# 2020-10-27_AD590_HIH-4031.net
KiCad netlist of a schematic drawn in EAGLE
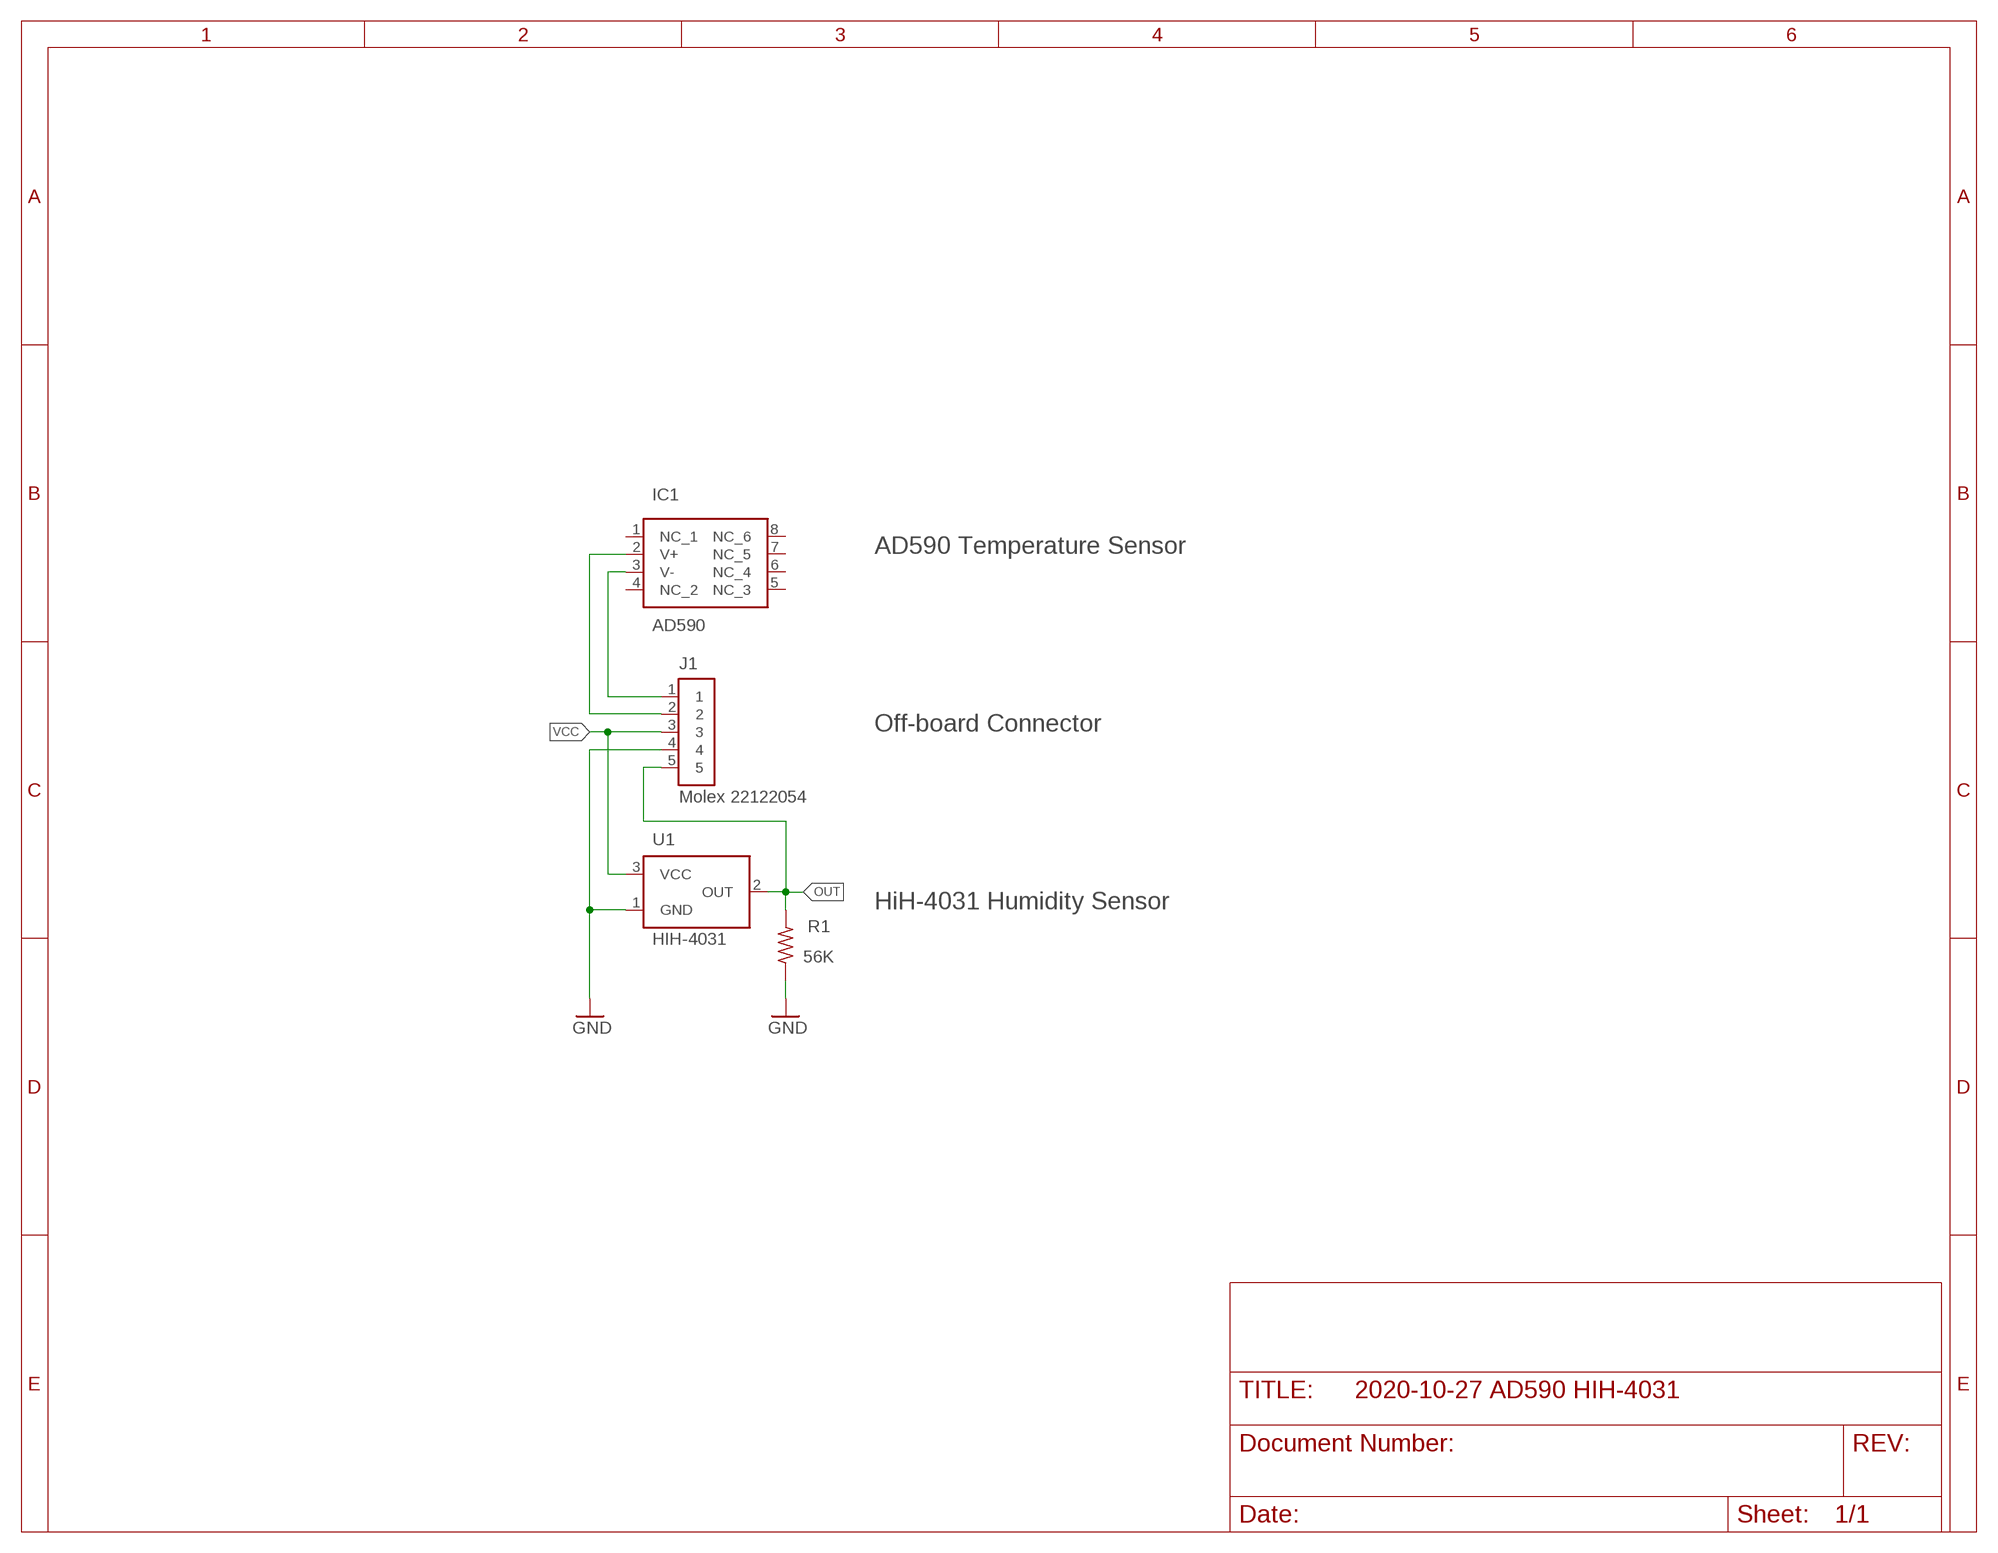
[diagram p0: schematic, sheet 1]

(export (version "E")
  (design (tool "Eeschema 10.0.6"))
  (components
    (comp (ref "IC1")
      (value "AD590")
      (footprint "eagle-import:SOIC127P600X175-8N")
      (fields
        (field (name "MANUFACTURER_PART_NUMBER") "AD590JRZ")
        (field (name "MOUSER_PART_NUMBER") "584-AD590JRZ")
        (field (name "RS_PART_NUMBER") "7096005P")
      )
      (libsource (lib "eagle-import") (part "AD590JRZ"))
    )
    (comp (ref "J1")
      (value "Molex 22122054")
      (footprint "eagle-import:1X05RA-MOLEX-22122054")
      (libsource (lib "eagle-import") (part "PINHD-1X5RA-MOLEX-22122054"))
    )
    (comp (ref "R1")
      (value "56K")
      (footprint "eagle-import:R0805")
      (libsource (lib "eagle-import") (part "R-US_R0805"))
    )
    (comp (ref "U1")
      (value "HIH-4031")
      (footprint "eagle-import:HIH-4030")
      (libsource (lib "eagle-import") (part "HIH-4030"))
    )
  )
  (nets
    (net (code "1") (name "GND") (class "Default")
      (node (ref "J1") (pin "4") (pinfunction "4_4") (pintype "bidirectional"))
      (node (ref "R1") (pin "1") (pinfunction "1_1") (pintype "passive"))
      (node (ref "U1") (pin "1") (pinfunction "GND_1") (pintype "bidirectional"))
    )
    (net (code "2") (name "Net-(IC1-V+)") (class "Default")
      (node (ref "IC1") (pin "2") (pinfunction "V+_2") (pintype "bidirectional"))
      (node (ref "J1") (pin "2") (pinfunction "2_2") (pintype "bidirectional"))
    )
    (net (code "3") (name "Net-(IC1-V-)") (class "Default")
      (node (ref "IC1") (pin "3") (pinfunction "V-_3") (pintype "bidirectional"))
      (node (ref "J1") (pin "1") (pinfunction "1_1") (pintype "bidirectional"))
    )
    (net (code "4") (name "OUT") (class "Default")
      (node (ref "J1") (pin "5") (pinfunction "5_5") (pintype "bidirectional"))
      (node (ref "R1") (pin "2") (pinfunction "2_2") (pintype "passive"))
      (node (ref "U1") (pin "2") (pinfunction "OUT_2") (pintype "bidirectional"))
    )
    (net (code "5") (name "VCC") (class "Default")
      (node (ref "J1") (pin "3") (pinfunction "3_3") (pintype "bidirectional"))
      (node (ref "U1") (pin "3") (pinfunction "VCC_3") (pintype "bidirectional"))
    )
    (net (code "6") (name "unconnected-(IC1-NC_1-Pad1)") (class "Default")
      (node (ref "IC1") (pin "1") (pinfunction "NC_1_1") (pintype "bidirectional"))
    )
    (net (code "7") (name "unconnected-(IC1-NC_2-Pad4)") (class "Default")
      (node (ref "IC1") (pin "4") (pinfunction "NC_2_4") (pintype "bidirectional"))
    )
    (net (code "8") (name "unconnected-(IC1-NC_3-Pad5)") (class "Default")
      (node (ref "IC1") (pin "5") (pinfunction "NC_3_5") (pintype "bidirectional"))
    )
    (net (code "9") (name "unconnected-(IC1-NC_4-Pad6)") (class "Default")
      (node (ref "IC1") (pin "6") (pinfunction "NC_4_6") (pintype "bidirectional"))
    )
    (net (code "10") (name "unconnected-(IC1-NC_5-Pad7)") (class "Default")
      (node (ref "IC1") (pin "7") (pinfunction "NC_5_7") (pintype "bidirectional"))
    )
    (net (code "11") (name "unconnected-(IC1-NC_6-Pad8)") (class "Default")
      (node (ref "IC1") (pin "8") (pinfunction "NC_6_8") (pintype "bidirectional"))
    )
  )
)
